# hcpl0630.net
KiCad netlist of a schematic drawn in Altium Designer
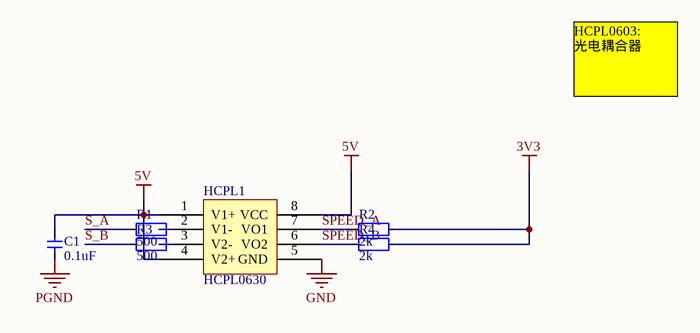
[diagram p0: hcpl0630.SchDoc]

(export (version "E")
  (design (tool "Eeschema 10.0.6"))
  (components
    (comp (ref "C1")
      (value "0.1uF")
      (footprint "CAP_0603")
      (description "Capacitor")
      (fields (field (name "Comment") "Cap_0603"))
      (libsource (lib "Integrated_Library") (part "Cap_0603"))
    )
    (comp (ref "HCPL1")
      (value "HCPL0630")
      (footprint "SOP_E150_8")
      (libsource (lib "K60-mainboard-v3.1") (part "HCPL0630"))
    )
    (comp (ref "R1")
      (value "500")
      (footprint "RES_0603")
      (description "Resistor")
      (fields (field (name "Comment") "Res_0603"))
      (libsource (lib "Integrated_Library") (part "Res_0603"))
    )
    (comp (ref "R2")
      (value "2k")
      (footprint "RES_0603")
      (description "Resistor")
      (fields (field (name "Comment") "Res_0603"))
      (libsource (lib "Integrated_Library") (part "Res_0603"))
    )
    (comp (ref "R3")
      (value "500")
      (footprint "RES_0603")
      (description "Resistor")
      (fields (field (name "Comment") "Res_0603"))
      (libsource (lib "Integrated_Library") (part "Res_0603"))
    )
    (comp (ref "R4")
      (value "2k")
      (footprint "RES_0603")
      (description "Resistor")
      (fields (field (name "Comment") "Res_0603"))
      (libsource (lib "Integrated_Library") (part "Res_0603"))
    )
  )
  (nets
    (net (code "1") (name "/SPEED_A") (class "Default")
      (node (ref "HCPL1") (pin "7") (pinfunction "VO1_7") (pintype "passive"))
      (node (ref "R2") (pin "2") (pinfunction "2_2") (pintype "passive"))
    )
    (net (code "2") (name "/SPEED_B") (class "Default")
      (node (ref "HCPL1") (pin "6") (pinfunction "VO2_6") (pintype "passive"))
      (node (ref "R4") (pin "2") (pinfunction "2_2") (pintype "passive"))
    )
    (net (code "3") (name "/S_A") (class "Default")
      (node (ref "R1") (pin "2") (pinfunction "2_2") (pintype "passive"))
    )
    (net (code "4") (name "/S_B") (class "Default")
      (node (ref "R3") (pin "2") (pinfunction "2_2") (pintype "passive"))
    )
    (net (code "5") (name "3V3") (class "Default")
      (node (ref "R2") (pin "1") (pinfunction "1_1") (pintype "passive"))
      (node (ref "R4") (pin "1") (pinfunction "1_1") (pintype "passive"))
    )
    (net (code "6") (name "5V") (class "Default")
      (node (ref "C1") (pin "2") (pinfunction "2_2") (pintype "passive"))
      (node (ref "HCPL1") (pin "1") (pinfunction "V1+_1") (pintype "passive"))
      (node (ref "HCPL1") (pin "4") (pinfunction "V2+_4") (pintype "passive"))
      (node (ref "HCPL1") (pin "8") (pinfunction "VCC_8") (pintype "passive"))
    )
    (net (code "7") (name "GND") (class "Default")
      (node (ref "HCPL1") (pin "5") (pinfunction "GND_5") (pintype "passive"))
    )
    (net (code "8") (name "Net-(HCPL1-V1-)") (class "Default")
      (node (ref "HCPL1") (pin "2") (pinfunction "V1-_2") (pintype "passive"))
      (node (ref "R1") (pin "1") (pinfunction "1_1") (pintype "passive"))
    )
    (net (code "9") (name "Net-(HCPL1-V2-)") (class "Default")
      (node (ref "HCPL1") (pin "3") (pinfunction "V2-_3") (pintype "passive"))
      (node (ref "R3") (pin "1") (pinfunction "1_1") (pintype "passive"))
    )
    (net (code "10") (name "PGND") (class "Default")
      (node (ref "C1") (pin "1") (pinfunction "1_1") (pintype "passive"))
    )
  )
)
